# ST_LINK.net
KiCad netlist of a schematic drawn in Altium Designer
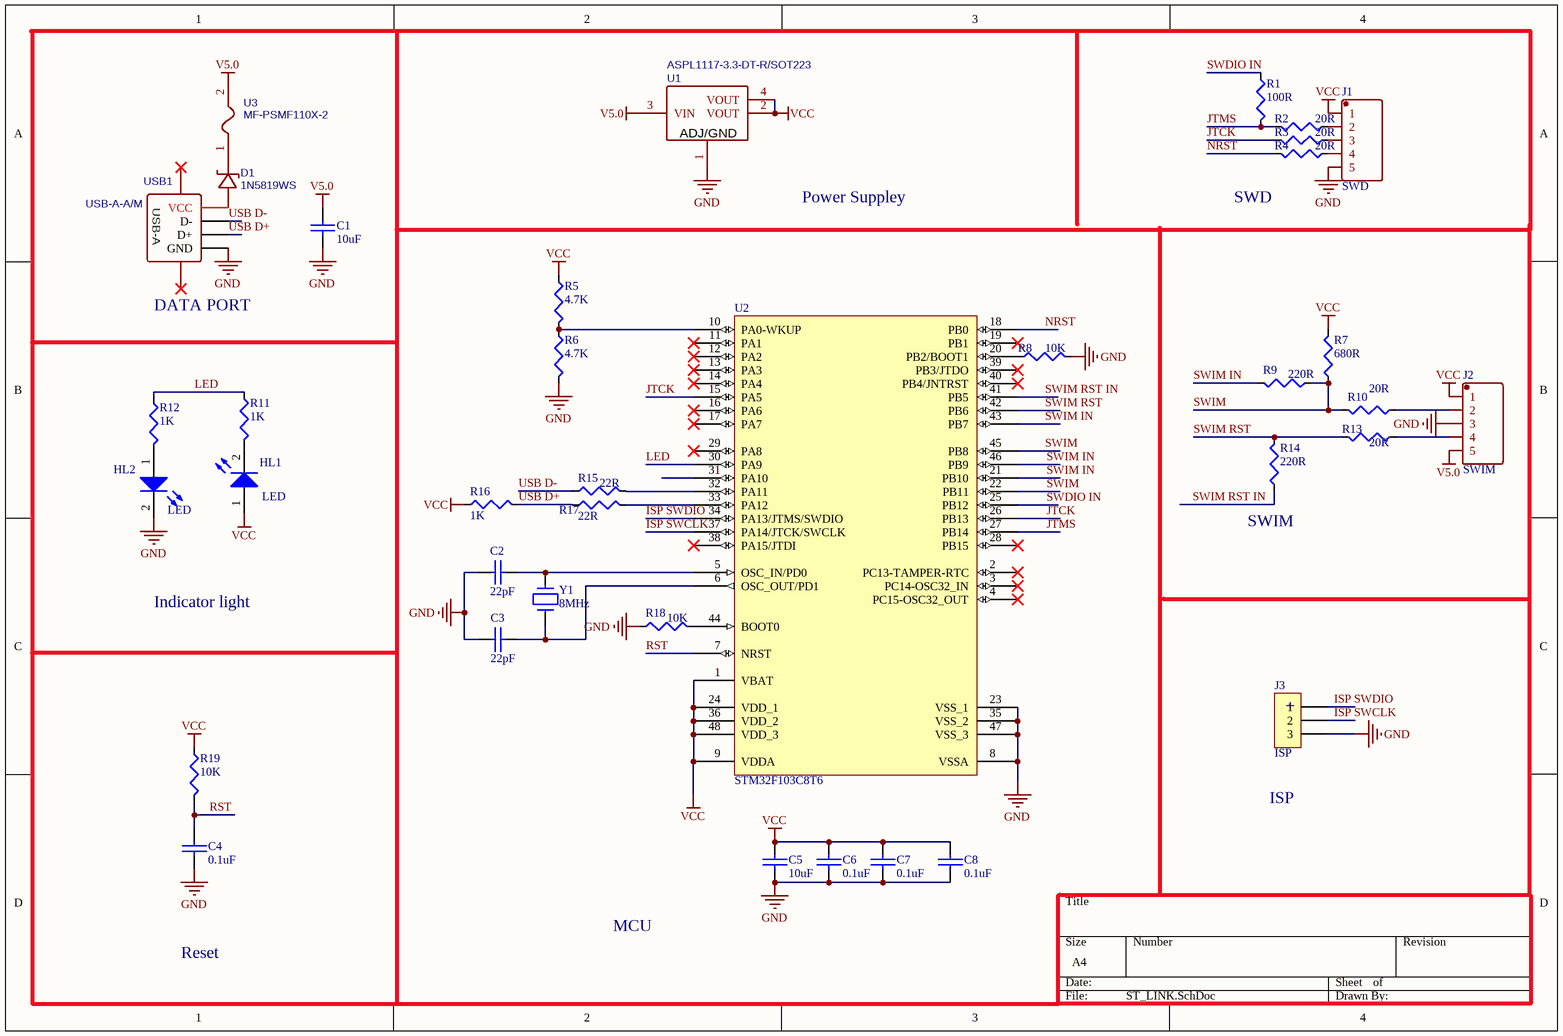
[diagram p0: ST_LINK.SchDoc]

(export (version "E")
  (design (tool "Eeschema 10.0.6"))
  (components
    (comp (ref "C1") (value "10uF") (footprint "0603-C") (libsource (lib "gedj") (part "C-0603")))
    (comp (ref "C2") (value "22pF") (footprint "0603-C") (libsource (lib "gedj") (part "C-0603")))
    (comp (ref "C3") (value "22pF") (footprint "0603-C") (libsource (lib "gedj") (part "C-0603")))
    (comp (ref "C4") (value "0.1uF") (footprint "0603-C") (libsource (lib "gedj") (part "C-0603")))
    (comp (ref "C5") (value "10uF") (footprint "0603-C") (libsource (lib "gedj") (part "C-0603")))
    (comp (ref "C6") (value "0.1uF") (footprint "0603-C") (libsource (lib "gedj") (part "C-0603")))
    (comp (ref "C7") (value "0.1uF") (footprint "0603-C") (libsource (lib "gedj") (part "C-0603")))
    (comp (ref "C8") (value "0.1uF") (footprint "0603-C") (libsource (lib "gedj") (part "C-0603")))
    (comp (ref "D1")
      (value "1N5819WS")
      (footprint "SOD-323_L1.8-W1.3-LS2.5-RD")
      (fields (field (name "BOM_SUPPLIER PART") "C191023") (field (name "CONTRIBUTOR") "LCSC"))
      (libsource (lib "gedj") (part "1N5819WS"))
    )
    (comp (ref "HL1")
      (value "LED")
      (footprint "LED-0805")
      (description "LED-0805-BLUE")
      (libsource (lib "gedj") (part "LED-0805-BLUE"))
    )
    (comp (ref "HL2")
      (value "LED")
      (footprint "LED-0805")
      (description "LED-0805-BLUE")
      (libsource (lib "gedj") (part "LED-0805-BLUE"))
    )
    (comp (ref "J1") (value "SWD") (footprint "牛角座") (libsource (lib "gedj") (part "CON-5*2.54")))
    (comp (ref "J2") (value "SWIM") (footprint "牛角座") (libsource (lib "gedj") (part "CON-5*2.54")))
    (comp (ref "J3") (value "ISP") (footprint "CON-3*2.54") (libsource (lib "gedj") (part "CON-3*2.54")))
    (comp (ref "R1") (value "100R") (footprint "R-0603") (libsource (lib "gedj") (part "R-0603")))
    (comp (ref "R2") (value "20R") (footprint "R-0603") (libsource (lib "gedj") (part "R-0603")))
    (comp (ref "R3") (value "20R") (footprint "R-0603") (libsource (lib "gedj") (part "R-0603")))
    (comp (ref "R4") (value "20R") (footprint "R-0603") (libsource (lib "gedj") (part "R-0603")))
    (comp (ref "R5") (value "4.7K") (footprint "R-0603") (libsource (lib "gedj") (part "R-0603")))
    (comp (ref "R6") (value "4.7K") (footprint "R-0603") (libsource (lib "gedj") (part "R-0603")))
    (comp (ref "R7") (value "680R") (footprint "R-0603") (libsource (lib "gedj") (part "R-0603")))
    (comp (ref "R8") (value "10K") (footprint "R-0603") (libsource (lib "gedj") (part "R-0603")))
    (comp (ref "R9") (value "220R") (footprint "R-0603") (libsource (lib "gedj") (part "R-0603")))
    (comp (ref "R10") (value "20R") (footprint "R-0603") (libsource (lib "gedj") (part "R-0603")))
    (comp (ref "R11") (value "1K") (footprint "R-0603") (libsource (lib "gedj") (part "R-0603")))
    (comp (ref "R12") (value "1K") (footprint "R-0603") (libsource (lib "gedj") (part "R-0603")))
    (comp (ref "R13") (value "20R") (footprint "R-0603") (libsource (lib "gedj") (part "R-0603")))
    (comp (ref "R14") (value "220R") (footprint "R-0603") (libsource (lib "gedj") (part "R-0603")))
    (comp (ref "R15") (value "22R") (footprint "R-0603") (libsource (lib "gedj") (part "R-0603")))
    (comp (ref "R16") (value "1K") (footprint "R-0603") (libsource (lib "gedj") (part "R-0603")))
    (comp (ref "R17") (value "22R") (footprint "R-0603") (libsource (lib "gedj") (part "R-0603")))
    (comp (ref "R18") (value "10K") (footprint "R-0603") (libsource (lib "gedj") (part "R-0603")))
    (comp (ref "R19") (value "10K") (footprint "R-0603") (libsource (lib "gedj") (part "R-0603")))
    (comp (ref "U1")
      (value "ASPL1117-3.3-DT-R/SOT223")
      (footprint "SOT223")
      (fields (field (name "BOM_SUPPLIER PART") "C520553") (field (name "CONTRIBUTOR") "LCSC"))
      (libsource (lib "gedj") (part "ASPL1117-3.3-DT-R/SOT223"))
    )
    (comp (ref "U2")
      (value "STM32F103C8T6")
      (footprint "LQFP-48_L7.0-W7.0-P0.50-LS9.0-BL")
      (libsource (lib "STM32系列") (part "STM32F103C8T6"))
    )
    (comp (ref "U3")
      (value "MF-PSMF110X-2")
      (footprint "F0805")
      (fields (field (name "BOM_SUPPLIER PART") "C89658"))
      (libsource (lib "gedj") (part "MF-PSMF110X-2"))
    )
    (comp (ref "USB1")
      (value "USB-A-A/M")
      (footprint "USB-A-SMD_USB-A-1-TH")
      (fields
        (field (name "BOM_MANUFACTURER PART") "A/M Stick plate bent legs VinylPBT With a column")
        (field (name "BOM_SUPPLIER PART") "C46394")
      )
      (libsource (lib "gedj") (part "USB-A-A/M Stick plate bent legs VinylPBT With a column"))
    )
    (comp (ref "Y1") (value "8MHz") (footprint "8M-crystals") (libsource (lib "gedj") (part "XTAT")))
  )
  (nets
    (net (code "1") (name "/ISP SWCLK") (class "Default")
      (node (ref "J3") (pin "2") (pinfunction "2_2") (pintype "passive"))
      (node (ref "U2") (pin "37") (pinfunction "PA14/JTCK/SWCLK_37") (pintype "bidirectional"))
    )
    (net (code "2") (name "/ISP SWDIO") (class "Default")
      (node (ref "J3") (pin "1") (pinfunction "1_1") (pintype "passive"))
      (node (ref "U2") (pin "34") (pinfunction "PA13/JTMS/SWDIO_34") (pintype "bidirectional"))
    )
    (net (code "3") (name "/JTCK") (class "Default")
      (node (ref "R3") (pin "2") (pinfunction "2_2") (pintype "passive"))
      (node (ref "U2") (pin "15") (pinfunction "PA5_15") (pintype "bidirectional"))
      (node (ref "U2") (pin "26") (pinfunction "PB13_26") (pintype "bidirectional"))
    )
    (net (code "4") (name "/JTMS") (class "Default")
      (node (ref "R1") (pin "2") (pinfunction "2_2") (pintype "passive"))
      (node (ref "R2") (pin "2") (pinfunction "2_2") (pintype "passive"))
      (node (ref "U2") (pin "27") (pinfunction "PB14_27") (pintype "bidirectional"))
    )
    (net (code "5") (name "/LED") (class "Default")
      (node (ref "R11") (pin "1") (pinfunction "1_1") (pintype "passive"))
      (node (ref "R12") (pin "1") (pinfunction "1_1") (pintype "passive"))
      (node (ref "U2") (pin "30") (pinfunction "PA9_30") (pintype "bidirectional"))
    )
    (net (code "6") (name "/NRST") (class "Default")
      (node (ref "R4") (pin "2") (pinfunction "2_2") (pintype "passive"))
      (node (ref "U2") (pin "18") (pinfunction "PB0_18") (pintype "bidirectional"))
    )
    (net (code "7") (name "/RST") (class "Default")
      (node (ref "C4") (pin "1") (pinfunction "1_1") (pintype "passive"))
      (node (ref "R19") (pin "2") (pinfunction "2_2") (pintype "passive"))
      (node (ref "U2") (pin "7") (pinfunction "NRST_7") (pintype "bidirectional"))
    )
    (net (code "8") (name "/SWDIO IN") (class "Default")
      (node (ref "R1") (pin "1") (pinfunction "1_1") (pintype "passive"))
      (node (ref "U2") (pin "25") (pinfunction "PB12_25") (pintype "bidirectional"))
    )
    (net (code "9") (name "/SWIM") (class "Default")
      (node (ref "R10") (pin "2") (pinfunction "2_2") (pintype "passive"))
      (node (ref "R7") (pin "1") (pinfunction "1_1") (pintype "passive"))
      (node (ref "R9") (pin "1") (pinfunction "1_1") (pintype "passive"))
      (node (ref "U2") (pin "22") (pinfunction "PB11_22") (pintype "bidirectional"))
      (node (ref "U2") (pin "45") (pinfunction "PB8_45") (pintype "bidirectional"))
    )
    (net (code "10") (name "/SWIM IN") (class "Default")
      (node (ref "R9") (pin "2") (pinfunction "2_2") (pintype "passive"))
      (node (ref "U2") (pin "21") (pinfunction "PB10_21") (pintype "bidirectional"))
      (node (ref "U2") (pin "43") (pinfunction "PB7_43") (pintype "bidirectional"))
      (node (ref "U2") (pin "46") (pinfunction "PB9_46") (pintype "bidirectional"))
    )
    (net (code "11") (name "/SWIM RST") (class "Default")
      (node (ref "R13") (pin "2") (pinfunction "2_2") (pintype "passive"))
      (node (ref "R14") (pin "2") (pinfunction "2_2") (pintype "passive"))
      (node (ref "U2") (pin "42") (pinfunction "PB6_42") (pintype "bidirectional"))
    )
    (net (code "12") (name "/SWIM RST IN") (class "Default")
      (node (ref "R14") (pin "1") (pinfunction "1_1") (pintype "passive"))
      (node (ref "U2") (pin "41") (pinfunction "PB5_41") (pintype "bidirectional"))
    )
    (net (code "13") (name "/USB D+") (class "Default")
      (node (ref "R16") (pin "2") (pinfunction "2_2") (pintype "passive"))
      (node (ref "R17") (pin "1") (pinfunction "1_1") (pintype "passive"))
      (node (ref "USB1") (pin "3") (pinfunction "D+_3") (pintype "passive"))
    )
    (net (code "14") (name "/USB D-") (class "Default")
      (node (ref "R15") (pin "1") (pinfunction "1_1") (pintype "passive"))
      (node (ref "USB1") (pin "2") (pinfunction "D-_2") (pintype "passive"))
    )
    (net (code "15") (name "GND") (class "Default")
      (node (ref "C1") (pin "1") (pinfunction "1_1") (pintype "passive"))
      (node (ref "C2") (pin "2") (pinfunction "2_2") (pintype "passive"))
      (node (ref "C3") (pin "1") (pinfunction "1_1") (pintype "passive"))
      (node (ref "C4") (pin "2") (pinfunction "2_2") (pintype "passive"))
      (node (ref "C5") (pin "1") (pinfunction "1_1") (pintype "passive"))
      (node (ref "C6") (pin "2") (pinfunction "2_2") (pintype "passive"))
      (node (ref "C7") (pin "2") (pinfunction "2_2") (pintype "passive"))
      (node (ref "C8") (pin "2") (pinfunction "2_2") (pintype "passive"))
      (node (ref "HL2") (pin "2") (pinfunction "K_2") (pintype "passive"))
      (node (ref "J1") (pin "5") (pinfunction "5_5") (pintype "passive"))
      (node (ref "J2") (pin "3") (pinfunction "3_3") (pintype "passive"))
      (node (ref "J3") (pin "3") (pinfunction "3_3") (pintype "passive"))
      (node (ref "R18") (pin "1") (pinfunction "1_1") (pintype "passive"))
      (node (ref "R6") (pin "2") (pinfunction "2_2") (pintype "passive"))
      (node (ref "R8") (pin "2") (pinfunction "2_2") (pintype "passive"))
      (node (ref "U1") (pin "1") (pinfunction "ADJ/GND_1") (pintype "passive"))
      (node (ref "U2") (pin "23") (pinfunction "VSS_1_23") (pintype "power_in"))
      (node (ref "U2") (pin "35") (pinfunction "VSS_2_35") (pintype "power_in"))
      (node (ref "U2") (pin "47") (pinfunction "VSS_3_47") (pintype "power_in"))
      (node (ref "U2") (pin "8") (pinfunction "VSSA_8") (pintype "power_in"))
      (node (ref "USB1") (pin "4") (pinfunction "GND_4") (pintype "passive"))
    )
    (net (code "16") (name "Net-(D1-A)") (class "Default")
      (node (ref "D1") (pin "2") (pinfunction "A_2") (pintype "passive"))
      (node (ref "USB1") (pin "1") (pinfunction "VCC_1") (pintype "passive"))
    )
    (net (code "17") (name "Net-(D1-C)") (class "Default")
      (node (ref "D1") (pin "1") (pinfunction "C_1") (pintype "passive"))
      (node (ref "U3") (pin "1") (pinfunction "1_1") (pintype "passive"))
    )
    (net (code "18") (name "Net-(HL1-K)") (class "Default")
      (node (ref "HL1") (pin "2") (pinfunction "K_2") (pintype "passive"))
      (node (ref "R11") (pin "2") (pinfunction "2_2") (pintype "passive"))
    )
    (net (code "19") (name "Net-(HL2-A)") (class "Default")
      (node (ref "HL2") (pin "1") (pinfunction "A_1") (pintype "passive"))
      (node (ref "R12") (pin "2") (pinfunction "2_2") (pintype "passive"))
    )
    (net (code "20") (name "Net-(J1-Pad2)") (class "Default")
      (node (ref "J1") (pin "2") (pinfunction "2_2") (pintype "passive"))
      (node (ref "R2") (pin "1") (pinfunction "1_1") (pintype "passive"))
    )
    (net (code "21") (name "Net-(J1-Pad3)") (class "Default")
      (node (ref "J1") (pin "3") (pinfunction "3_3") (pintype "passive"))
      (node (ref "R3") (pin "1") (pinfunction "1_1") (pintype "passive"))
    )
    (net (code "22") (name "Net-(J1-Pad4)") (class "Default")
      (node (ref "J1") (pin "4") (pinfunction "4_4") (pintype "passive"))
      (node (ref "R4") (pin "1") (pinfunction "1_1") (pintype "passive"))
    )
    (net (code "23") (name "Net-(J2-Pad2)") (class "Default")
      (node (ref "J2") (pin "2") (pinfunction "2_2") (pintype "passive"))
      (node (ref "R10") (pin "1") (pinfunction "1_1") (pintype "passive"))
    )
    (net (code "24") (name "Net-(J2-Pad4)") (class "Default")
      (node (ref "J2") (pin "4") (pinfunction "4_4") (pintype "passive"))
      (node (ref "R13") (pin "1") (pinfunction "1_1") (pintype "passive"))
    )
    (net (code "25") (name "Net-(U2-BOOT0)") (class "Default")
      (node (ref "R18") (pin "2") (pinfunction "2_2") (pintype "passive"))
      (node (ref "U2") (pin "44") (pinfunction "BOOT0_44") (pintype "input"))
    )
    (net (code "26") (name "Net-(U2-OSC_IN{slash}PD0)") (class "Default")
      (node (ref "C2") (pin "1") (pinfunction "1_1") (pintype "passive"))
      (node (ref "U2") (pin "5") (pinfunction "OSC_IN/PD0_5") (pintype "input"))
      (node (ref "Y1") (pin "2") (pinfunction "2_2") (pintype "passive"))
    )
    (net (code "27") (name "Net-(U2-OSC_OUT{slash}PD1)") (class "Default")
      (node (ref "C3") (pin "2") (pinfunction "2_2") (pintype "passive"))
      (node (ref "U2") (pin "6") (pinfunction "OSC_OUT/PD1_6") (pintype "output"))
      (node (ref "Y1") (pin "1") (pinfunction "1_1") (pintype "passive"))
    )
    (net (code "28") (name "Net-(U2-PA0-WKUP)") (class "Default")
      (node (ref "R5") (pin "2") (pinfunction "2_2") (pintype "passive"))
      (node (ref "R6") (pin "1") (pinfunction "1_1") (pintype "passive"))
      (node (ref "U2") (pin "10") (pinfunction "PA0-WKUP_10") (pintype "bidirectional"))
    )
    (net (code "29") (name "Net-(U2-PA11)") (class "Default")
      (node (ref "R15") (pin "2") (pinfunction "2_2") (pintype "passive"))
      (node (ref "U2") (pin "32") (pinfunction "PA11_32") (pintype "bidirectional"))
    )
    (net (code "30") (name "Net-(U2-PA12)") (class "Default")
      (node (ref "R17") (pin "2") (pinfunction "2_2") (pintype "passive"))
      (node (ref "U2") (pin "33") (pinfunction "PA12_33") (pintype "bidirectional"))
    )
    (net (code "31") (name "Net-(U2-PB2{slash}BOOT1)") (class "Default")
      (node (ref "R8") (pin "1") (pinfunction "1_1") (pintype "passive"))
      (node (ref "U2") (pin "20") (pinfunction "PB2/BOOT1_20") (pintype "bidirectional"))
    )
    (net (code "32") (name "V5.0") (class "Default")
      (node (ref "C1") (pin "2") (pinfunction "2_2") (pintype "passive"))
      (node (ref "J2") (pin "5") (pinfunction "5_5") (pintype "passive"))
      (node (ref "U1") (pin "3") (pinfunction "VIN_3") (pintype "passive"))
      (node (ref "U3") (pin "2") (pinfunction "2_2") (pintype "passive"))
    )
    (net (code "33") (name "VCC") (class "Default")
      (node (ref "C5") (pin "2") (pinfunction "2_2") (pintype "passive"))
      (node (ref "C6") (pin "1") (pinfunction "1_1") (pintype "passive"))
      (node (ref "C7") (pin "1") (pinfunction "1_1") (pintype "passive"))
      (node (ref "C8") (pin "1") (pinfunction "1_1") (pintype "passive"))
      (node (ref "HL1") (pin "1") (pinfunction "A_1") (pintype "passive"))
      (node (ref "J1") (pin "1") (pinfunction "1_1") (pintype "passive"))
      (node (ref "J2") (pin "1") (pinfunction "1_1") (pintype "passive"))
      (node (ref "R16") (pin "1") (pinfunction "1_1") (pintype "passive"))
      (node (ref "R19") (pin "1") (pinfunction "1_1") (pintype "passive"))
      (node (ref "R5") (pin "1") (pinfunction "1_1") (pintype "passive"))
      (node (ref "R7") (pin "2") (pinfunction "2_2") (pintype "passive"))
      (node (ref "U1") (pin "2") (pinfunction "VOUT_2") (pintype "passive"))
      (node (ref "U1") (pin "4") (pinfunction "VOUT_4") (pintype "passive"))
      (node (ref "U2") (pin "1") (pinfunction "VBAT_1") (pintype "power_in"))
      (node (ref "U2") (pin "24") (pinfunction "VDD_1_24") (pintype "power_in"))
      (node (ref "U2") (pin "36") (pinfunction "VDD_2_36") (pintype "power_in"))
      (node (ref "U2") (pin "48") (pinfunction "VDD_3_48") (pintype "power_in"))
      (node (ref "U2") (pin "9") (pinfunction "VDDA_9") (pintype "power_in"))
    )
    (net (code "34") (name "unconnected-(U2-PA1-Pad11)") (class "Default")
      (node (ref "U2") (pin "11") (pinfunction "PA1_11") (pintype "bidirectional+no_connect"))
    )
    (net (code "35") (name "unconnected-(U2-PA2-Pad12)") (class "Default")
      (node (ref "U2") (pin "12") (pinfunction "PA2_12") (pintype "bidirectional+no_connect"))
    )
    (net (code "36") (name "unconnected-(U2-PA3-Pad13)") (class "Default")
      (node (ref "U2") (pin "13") (pinfunction "PA3_13") (pintype "bidirectional+no_connect"))
    )
    (net (code "37") (name "unconnected-(U2-PA4-Pad14)") (class "Default")
      (node (ref "U2") (pin "14") (pinfunction "PA4_14") (pintype "bidirectional+no_connect"))
    )
    (net (code "38") (name "unconnected-(U2-PA6-Pad16)") (class "Default")
      (node (ref "U2") (pin "16") (pinfunction "PA6_16") (pintype "bidirectional+no_connect"))
    )
    (net (code "39") (name "unconnected-(U2-PA7-Pad17)") (class "Default")
      (node (ref "U2") (pin "17") (pinfunction "PA7_17") (pintype "bidirectional+no_connect"))
    )
    (net (code "40") (name "unconnected-(U2-PA8-Pad29)") (class "Default")
      (node (ref "U2") (pin "29") (pinfunction "PA8_29") (pintype "bidirectional+no_connect"))
    )
    (net (code "41") (name "unconnected-(U2-PA10-Pad31)") (class "Default")
      (node (ref "U2") (pin "31") (pinfunction "PA10_31") (pintype "bidirectional"))
    )
    (net (code "42") (name "unconnected-(U2-PA15{slash}JTDI-Pad38)") (class "Default")
      (node (ref "U2") (pin "38") (pinfunction "PA15/JTDI_38") (pintype "bidirectional+no_connect"))
    )
    (net (code "43") (name "unconnected-(U2-PB1-Pad19)") (class "Default")
      (node (ref "U2") (pin "19") (pinfunction "PB1_19") (pintype "bidirectional+no_connect"))
    )
    (net (code "44") (name "unconnected-(U2-PB3{slash}JTDO-Pad39)") (class "Default")
      (node (ref "U2") (pin "39") (pinfunction "PB3/JTDO_39") (pintype "bidirectional+no_connect"))
    )
    (net (code "45") (name "unconnected-(U2-PB4{slash}JNTRST-Pad40)") (class "Default")
      (node (ref "U2") (pin "40") (pinfunction "PB4/JNTRST_40") (pintype "bidirectional+no_connect"))
    )
    (net (code "46") (name "unconnected-(U2-PB15-Pad28)") (class "Default")
      (node (ref "U2") (pin "28") (pinfunction "PB15_28") (pintype "bidirectional+no_connect"))
    )
    (net (code "47") (name "unconnected-(U2-PC13-TAMPER-RTC-Pad2)") (class "Default")
      (node (ref "U2") (pin "2") (pinfunction "PC13-TAMPER-RTC_2") (pintype "bidirectional+no_connect"))
    )
    (net (code "48") (name "unconnected-(U2-PC14-OSC32_IN-Pad3)") (class "Default")
      (node (ref "U2") (pin "3") (pinfunction "PC14-OSC32_IN_3") (pintype "bidirectional+no_connect"))
    )
    (net (code "49") (name "unconnected-(U2-PC15-OSC32_OUT-Pad4)") (class "Default")
      (node (ref "U2") (pin "4") (pinfunction "PC15-OSC32_OUT_4") (pintype "bidirectional+no_connect"))
    )
    (net (code "50") (name "unconnected-(USB1-Pad5)") (class "Default")
      (node (ref "USB1") (pin "5") (pinfunction "5_5") (pintype "passive+no_connect"))
    )
    (net (code "51") (name "unconnected-(USB1-Pad6)") (class "Default")
      (node (ref "USB1") (pin "6") (pinfunction "6_6") (pintype "passive+no_connect"))
    )
  )
)
